# prozeda_0_1.net
KiCad netlist of a schematic drawn in EAGLE
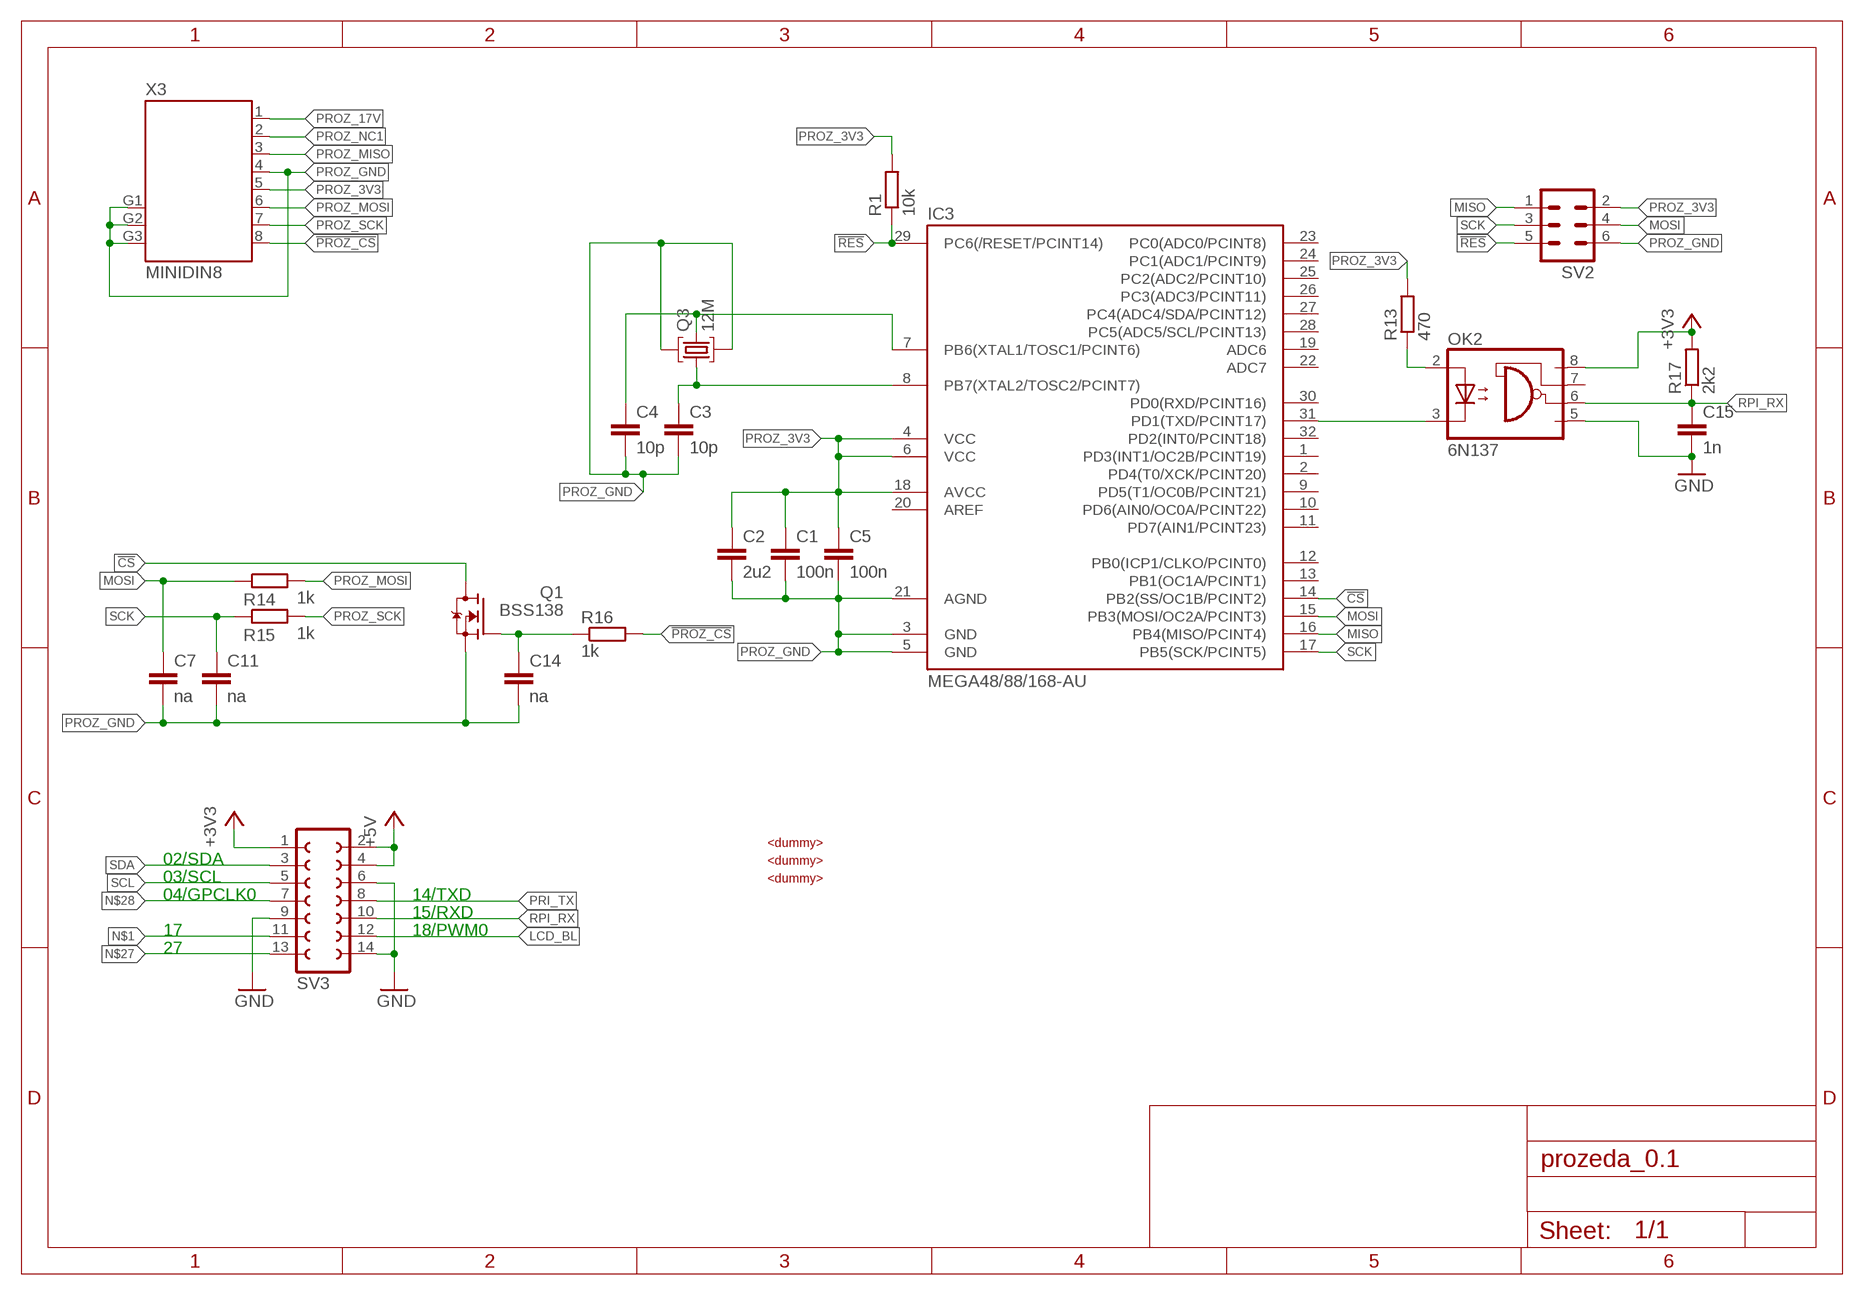
[diagram p0: schematic, sheet 1]

(export (version "E")
  (design (tool "Eeschema 10.0.6"))
  (components
    (comp (ref "C1")
      (value "100n")
      (footprint "eagle-import:C0603")
      (libsource (lib "eagle-import") (part "C-EUC0603"))
    )
    (comp (ref "C2")
      (value "2u2")
      (footprint "eagle-import:C0805")
      (libsource (lib "eagle-import") (part "C-EUC0805"))
    )
    (comp (ref "C3")
      (value "10p")
      (footprint "eagle-import:C0603")
      (libsource (lib "eagle-import") (part "C-EUC0603"))
    )
    (comp (ref "C4")
      (value "10p")
      (footprint "eagle-import:C0603")
      (libsource (lib "eagle-import") (part "C-EUC0603"))
    )
    (comp (ref "C5")
      (value "100n")
      (footprint "eagle-import:C0603")
      (libsource (lib "eagle-import") (part "C-EUC0603"))
    )
    (comp (ref "C7")
      (value "na")
      (footprint "eagle-import:C0603")
      (libsource (lib "eagle-import") (part "C-EUC0603"))
    )
    (comp (ref "C11")
      (value "na")
      (footprint "eagle-import:C0603")
      (libsource (lib "eagle-import") (part "C-EUC0603"))
    )
    (comp (ref "C14")
      (value "na")
      (footprint "eagle-import:C0603")
      (libsource (lib "eagle-import") (part "C-EUC0603"))
    )
    (comp (ref "C15")
      (value "1n")
      (footprint "eagle-import:C0603")
      (libsource (lib "eagle-import") (part "C-EUC0603"))
    )
    (comp (ref "IC3")
      (value "MEGA48/88/168-AU")
      (footprint "eagle-import:TQFP32-08")
      (libsource (lib "eagle-import") (part "MEGA48/88/168-AU"))
    )
    (comp (ref "OK2")
      (value "6N137")
      (footprint "eagle-import:DIL08")
      (libsource (lib "eagle-import") (part "6N137"))
    )
    (comp (ref "Q1")
      (value "BSS138")
      (footprint "eagle-import:SOT23")
      (libsource (lib "eagle-import") (part "BSS138"))
    )
    (comp (ref "Q3")
      (value "12M")
      (footprint "eagle-import:MJ")
      (libsource (lib "eagle-import") (part "SMD4PADMJ"))
    )
    (comp (ref "R1")
      (value "10k")
      (footprint "eagle-import:R0603")
      (libsource (lib "eagle-import") (part "R-EU_R0603"))
    )
    (comp (ref "R13")
      (value "470")
      (footprint "eagle-import:R0603")
      (libsource (lib "eagle-import") (part "R-EU_R0603"))
    )
    (comp (ref "R14")
      (value "1k")
      (footprint "eagle-import:R0603")
      (libsource (lib "eagle-import") (part "R-EU_R0603"))
    )
    (comp (ref "R15")
      (value "1k")
      (footprint "eagle-import:R0603")
      (libsource (lib "eagle-import") (part "R-EU_R0603"))
    )
    (comp (ref "R16")
      (value "1k")
      (footprint "eagle-import:R0603")
      (libsource (lib "eagle-import") (part "R-EU_R0603"))
    )
    (comp (ref "R17")
      (value "2k2")
      (footprint "eagle-import:R0603")
      (libsource (lib "eagle-import") (part "R-EU_R0603"))
    )
    (comp (ref "SV2")
      (value "MA03-2")
      (footprint "eagle-import:MA03-2")
      (libsource (lib "eagle-import") (part "MA03-2"))
    )
    (comp (ref "SV3")
      (value "FE07-2")
      (footprint "eagle-import:FE07-2")
      (libsource (lib "eagle-import") (part "FE07-2"))
    )
    (comp (ref "U$1")
      (value "DUMMY")
      (footprint "eagle-import:DUMMY")
      (libsource (lib "eagle-import") (part "DUMMY"))
    )
    (comp (ref "U$2")
      (value "DUMMY")
      (footprint "eagle-import:DUMMY")
      (libsource (lib "eagle-import") (part "DUMMY"))
    )
    (comp (ref "U$3")
      (value "DUMMY")
      (footprint "eagle-import:DUMMY")
      (libsource (lib "eagle-import") (part "DUMMY"))
    )
    (comp (ref "X3")
      (value "MINIDIN8")
      (footprint "eagle-import:MINI-DIN8")
      (libsource (lib "eagle-import") (part "MINIDIN8"))
    )
  )
  (nets
    (net (code "1") (name "+3V3") (class "Default")
      (node (ref "OK2") (pin "8") (pinfunction "VCC_8") (pintype "passive"))
      (node (ref "R17") (pin "2") (pinfunction "2_2") (pintype "passive"))
      (node (ref "SV3") (pin "1") (pinfunction "1_1") (pintype "passive"))
    )
    (net (code "2") (name "+5V") (class "Default")
      (node (ref "SV3") (pin "2") (pinfunction "2_2") (pintype "passive"))
      (node (ref "SV3") (pin "4") (pinfunction "4_4") (pintype "passive"))
    )
    (net (code "3") (name "/~{CS}") (class "Default")
      (node (ref "IC3") (pin "14") (pinfunction "PB2(SS/OC1B/PCINT2)_14") (pintype "bidirectional"))
      (node (ref "Q1") (pin "3") (pinfunction "D_3") (pintype "passive"))
    )
    (net (code "4") (name "/~{PROZ_CS}") (class "Default")
      (node (ref "R16") (pin "2") (pinfunction "2_2") (pintype "passive"))
      (node (ref "X3") (pin "8") (pinfunction "P$8_8") (pintype "bidirectional"))
    )
    (net (code "5") (name "/~{RES}") (class "Default")
      (node (ref "IC3") (pin "29") (pinfunction "PC6(/RESET/PCINT14)_29") (pintype "bidirectional"))
      (node (ref "R1") (pin "1") (pinfunction "1_1") (pintype "passive"))
      (node (ref "SV2") (pin "5") (pinfunction "5_5") (pintype "passive"))
    )
    (net (code "6") (name "GND") (class "Default")
      (node (ref "C15") (pin "2") (pinfunction "2_2") (pintype "passive"))
      (node (ref "OK2") (pin "5") (pinfunction "GND_5") (pintype "passive"))
      (node (ref "SV3") (pin "14") (pinfunction "14_14") (pintype "passive"))
      (node (ref "SV3") (pin "6") (pinfunction "6_6") (pintype "passive"))
      (node (ref "SV3") (pin "9") (pinfunction "9_9") (pintype "passive"))
    )
    (net (code "7") (name "LCD_BL") (class "Default")
      (node (ref "SV3") (pin "12") (pinfunction "12_12") (pintype "passive"))
    )
    (net (code "8") (name "MISO") (class "Default")
      (node (ref "IC3") (pin "16") (pinfunction "PB4(MISO/PCINT4)_16") (pintype "bidirectional"))
      (node (ref "SV2") (pin "1") (pinfunction "1_1") (pintype "passive"))
    )
    (net (code "9") (name "MOSI") (class "Default")
      (node (ref "C7") (pin "1") (pinfunction "1_1") (pintype "passive"))
      (node (ref "IC3") (pin "15") (pinfunction "PB3(MOSI/OC2A/PCINT3)_15") (pintype "bidirectional"))
      (node (ref "R14") (pin "1") (pinfunction "1_1") (pintype "passive"))
      (node (ref "SV2") (pin "4") (pinfunction "4_4") (pintype "passive"))
    )
    (net (code "10") (name "N$1") (class "Default")
      (node (ref "SV3") (pin "11") (pinfunction "11_11") (pintype "passive"))
    )
    (net (code "11") (name "N$27") (class "Default")
      (node (ref "SV3") (pin "13") (pinfunction "13_13") (pintype "passive"))
    )
    (net (code "12") (name "N$28") (class "Default")
      (node (ref "SV3") (pin "7") (pinfunction "7_7") (pintype "passive"))
    )
    (net (code "13") (name "Net-(IC3-PB6(XTAL1{slash}TOSC1{slash}PCINT6))") (class "Default")
      (node (ref "C4") (pin "1") (pinfunction "1_1") (pintype "passive"))
      (node (ref "IC3") (pin "7") (pinfunction "PB6(XTAL1/TOSC1/PCINT6)_7") (pintype "bidirectional"))
      (node (ref "Q3") (pin "3") (pinfunction "3_3") (pintype "passive"))
    )
    (net (code "14") (name "Net-(IC3-PB7(XTAL2{slash}TOSC2{slash}PCINT7))") (class "Default")
      (node (ref "C3") (pin "1") (pinfunction "1_1") (pintype "passive"))
      (node (ref "IC3") (pin "8") (pinfunction "PB7(XTAL2/TOSC2/PCINT7)_8") (pintype "bidirectional"))
      (node (ref "Q3") (pin "1") (pinfunction "1_1") (pintype "passive"))
    )
    (net (code "15") (name "Net-(IC3-PD1(TXD{slash}PCINT17))") (class "Default")
      (node (ref "IC3") (pin "31") (pinfunction "PD1(TXD/PCINT17)_31") (pintype "bidirectional"))
      (node (ref "OK2") (pin "3") (pinfunction "C_3") (pintype "passive"))
    )
    (net (code "16") (name "Net-(OK2-A)") (class "Default")
      (node (ref "OK2") (pin "2") (pinfunction "A_2") (pintype "passive"))
      (node (ref "R13") (pin "1") (pinfunction "1_1") (pintype "passive"))
    )
    (net (code "17") (name "Net-(Q1-G)") (class "Default")
      (node (ref "C14") (pin "1") (pinfunction "1_1") (pintype "passive"))
      (node (ref "Q1") (pin "1") (pinfunction "G_1") (pintype "passive"))
      (node (ref "R16") (pin "1") (pinfunction "1_1") (pintype "passive"))
    )
    (net (code "18") (name "PRI_TX") (class "Default")
      (node (ref "SV3") (pin "8") (pinfunction "8_8") (pintype "passive"))
    )
    (net (code "19") (name "PROZ_3V3") (class "Default")
      (node (ref "C1") (pin "1") (pinfunction "1_1") (pintype "passive"))
      (node (ref "C2") (pin "1") (pinfunction "1_1") (pintype "passive"))
      (node (ref "C5") (pin "1") (pinfunction "1_1") (pintype "passive"))
      (node (ref "IC3") (pin "18") (pinfunction "AVCC_18") (pintype "passive"))
      (node (ref "IC3") (pin "4") (pinfunction "VCC_4") (pintype "power_in"))
      (node (ref "IC3") (pin "6") (pinfunction "VCC_6") (pintype "power_in"))
      (node (ref "R1") (pin "2") (pinfunction "2_2") (pintype "passive"))
      (node (ref "R13") (pin "2") (pinfunction "2_2") (pintype "passive"))
      (node (ref "SV2") (pin "2") (pinfunction "2_2") (pintype "passive"))
      (node (ref "X3") (pin "5") (pinfunction "P$5_5") (pintype "bidirectional"))
    )
    (net (code "20") (name "PROZ_17V") (class "Default")
      (node (ref "X3") (pin "1") (pinfunction "P$1_1") (pintype "bidirectional"))
    )
    (net (code "21") (name "PROZ_GND") (class "Default")
      (node (ref "C1") (pin "2") (pinfunction "2_2") (pintype "passive"))
      (node (ref "C11") (pin "2") (pinfunction "2_2") (pintype "passive"))
      (node (ref "C14") (pin "2") (pinfunction "2_2") (pintype "passive"))
      (node (ref "C2") (pin "2") (pinfunction "2_2") (pintype "passive"))
      (node (ref "C3") (pin "2") (pinfunction "2_2") (pintype "passive"))
      (node (ref "C4") (pin "2") (pinfunction "2_2") (pintype "passive"))
      (node (ref "C5") (pin "2") (pinfunction "2_2") (pintype "passive"))
      (node (ref "C7") (pin "2") (pinfunction "2_2") (pintype "passive"))
      (node (ref "IC3") (pin "21") (pinfunction "AGND_21") (pintype "power_in"))
      (node (ref "IC3") (pin "3") (pinfunction "GND_3") (pintype "power_in"))
      (node (ref "IC3") (pin "5") (pinfunction "GND_5") (pintype "power_in"))
      (node (ref "Q1") (pin "2") (pinfunction "S_2") (pintype "passive"))
      (node (ref "Q3") (pin "2") (pinfunction "2_2") (pintype "passive"))
      (node (ref "Q3") (pin "4") (pinfunction "4_4") (pintype "passive"))
      (node (ref "SV2") (pin "6") (pinfunction "6_6") (pintype "passive"))
      (node (ref "X3") (pin "4") (pinfunction "P$4_4") (pintype "bidirectional"))
      (node (ref "X3") (pin "G1") (pinfunction "P$9_G1") (pintype "bidirectional"))
      (node (ref "X3") (pin "G2") (pinfunction "P$10_G2") (pintype "bidirectional"))
      (node (ref "X3") (pin "G3") (pinfunction "P$11_G3") (pintype "bidirectional"))
    )
    (net (code "22") (name "PROZ_MISO") (class "Default")
      (node (ref "X3") (pin "3") (pinfunction "P$3_3") (pintype "bidirectional"))
    )
    (net (code "23") (name "PROZ_MOSI") (class "Default")
      (node (ref "R14") (pin "2") (pinfunction "2_2") (pintype "passive"))
      (node (ref "X3") (pin "6") (pinfunction "P$6_6") (pintype "bidirectional"))
    )
    (net (code "24") (name "PROZ_NC1") (class "Default")
      (node (ref "X3") (pin "2") (pinfunction "P$2_2") (pintype "bidirectional"))
    )
    (net (code "25") (name "PROZ_SCK") (class "Default")
      (node (ref "R15") (pin "2") (pinfunction "2_2") (pintype "passive"))
      (node (ref "X3") (pin "7") (pinfunction "P$7_7") (pintype "bidirectional"))
    )
    (net (code "26") (name "RPI_RX") (class "Default")
      (node (ref "C15") (pin "1") (pinfunction "1_1") (pintype "passive"))
      (node (ref "OK2") (pin "6") (pinfunction "VO_6") (pintype "passive"))
      (node (ref "R17") (pin "1") (pinfunction "1_1") (pintype "passive"))
      (node (ref "SV3") (pin "10") (pinfunction "10_10") (pintype "passive"))
    )
    (net (code "27") (name "SCK") (class "Default")
      (node (ref "C11") (pin "1") (pinfunction "1_1") (pintype "passive"))
      (node (ref "IC3") (pin "17") (pinfunction "PB5(SCK/PCINT5)_17") (pintype "bidirectional"))
      (node (ref "R15") (pin "1") (pinfunction "1_1") (pintype "passive"))
      (node (ref "SV2") (pin "3") (pinfunction "3_3") (pintype "passive"))
    )
    (net (code "28") (name "SCL") (class "Default")
      (node (ref "SV3") (pin "5") (pinfunction "5_5") (pintype "passive"))
    )
    (net (code "29") (name "SDA") (class "Default")
      (node (ref "SV3") (pin "3") (pinfunction "3_3") (pintype "passive"))
    )
    (net (code "30") (name "unconnected-(IC3-ADC6-Pad19)") (class "Default")
      (node (ref "IC3") (pin "19") (pinfunction "ADC6_19") (pintype "passive"))
    )
    (net (code "31") (name "unconnected-(IC3-ADC7-Pad22)") (class "Default")
      (node (ref "IC3") (pin "22") (pinfunction "ADC7_22") (pintype "passive"))
    )
    (net (code "32") (name "unconnected-(IC3-AREF-Pad20)") (class "Default")
      (node (ref "IC3") (pin "20") (pinfunction "AREF_20") (pintype "passive"))
    )
    (net (code "33") (name "unconnected-(IC3-PB0(ICP1{slash}CLKO{slash}PCINT0)-Pad12)") (class "Default")
      (node (ref "IC3") (pin "12") (pinfunction "PB0(ICP1/CLKO/PCINT0)_12") (pintype "bidirectional"))
    )
    (net (code "34") (name "unconnected-(IC3-PB1(OC1A{slash}PCINT1)-Pad13)") (class "Default")
      (node (ref "IC3") (pin "13") (pinfunction "PB1(OC1A/PCINT1)_13") (pintype "bidirectional"))
    )
    (net (code "35") (name "unconnected-(IC3-PC0(ADC0{slash}PCINT8)-Pad23)") (class "Default")
      (node (ref "IC3") (pin "23") (pinfunction "PC0(ADC0/PCINT8)_23") (pintype "bidirectional"))
    )
    (net (code "36") (name "unconnected-(IC3-PC1(ADC1{slash}PCINT9)-Pad24)") (class "Default")
      (node (ref "IC3") (pin "24") (pinfunction "PC1(ADC1/PCINT9)_24") (pintype "bidirectional"))
    )
    (net (code "37") (name "unconnected-(IC3-PC2(ADC2{slash}PCINT10)-Pad25)") (class "Default")
      (node (ref "IC3") (pin "25") (pinfunction "PC2(ADC2/PCINT10)_25") (pintype "bidirectional"))
    )
    (net (code "38") (name "unconnected-(IC3-PC3(ADC3{slash}PCINT11)-Pad26)") (class "Default")
      (node (ref "IC3") (pin "26") (pinfunction "PC3(ADC3/PCINT11)_26") (pintype "bidirectional"))
    )
    (net (code "39") (name "unconnected-(IC3-PC4(ADC4{slash}SDA{slash}PCINT12)-Pad27)") (class "Default")
      (node (ref "IC3") (pin "27") (pinfunction "PC4(ADC4/SDA/PCINT12)_27") (pintype "bidirectional"))
    )
    (net (code "40") (name "unconnected-(IC3-PC5(ADC5{slash}SCL{slash}PCINT13)-Pad28)") (class "Default")
      (node (ref "IC3") (pin "28") (pinfunction "PC5(ADC5/SCL/PCINT13)_28") (pintype "bidirectional"))
    )
    (net (code "41") (name "unconnected-(IC3-PD0(RXD{slash}PCINT16)-Pad30)") (class "Default")
      (node (ref "IC3") (pin "30") (pinfunction "PD0(RXD/PCINT16)_30") (pintype "bidirectional"))
    )
    (net (code "42") (name "unconnected-(IC3-PD2(INT0{slash}PCINT18)-Pad32)") (class "Default")
      (node (ref "IC3") (pin "32") (pinfunction "PD2(INT0/PCINT18)_32") (pintype "bidirectional"))
    )
    (net (code "43") (name "unconnected-(IC3-PD3(INT1{slash}OC2B{slash}PCINT19)-Pad1)") (class "Default")
      (node (ref "IC3") (pin "1") (pinfunction "PD3(INT1/OC2B/PCINT19)_1") (pintype "bidirectional"))
    )
    (net (code "44") (name "unconnected-(IC3-PD4(T0{slash}XCK{slash}PCINT20)-Pad2)") (class "Default")
      (node (ref "IC3") (pin "2") (pinfunction "PD4(T0/XCK/PCINT20)_2") (pintype "bidirectional"))
    )
    (net (code "45") (name "unconnected-(IC3-PD5(T1{slash}OC0B{slash}PCINT21)-Pad9)") (class "Default")
      (node (ref "IC3") (pin "9") (pinfunction "PD5(T1/OC0B/PCINT21)_9") (pintype "bidirectional"))
    )
    (net (code "46") (name "unconnected-(IC3-PD6(AIN0{slash}OC0A{slash}PCINT22)-Pad10)") (class "Default")
      (node (ref "IC3") (pin "10") (pinfunction "PD6(AIN0/OC0A/PCINT22)_10") (pintype "bidirectional"))
    )
    (net (code "47") (name "unconnected-(IC3-PD7(AIN1{slash}PCINT23)-Pad11)") (class "Default")
      (node (ref "IC3") (pin "11") (pinfunction "PD7(AIN1/PCINT23)_11") (pintype "bidirectional"))
    )
    (net (code "48") (name "unconnected-(OK2-VE-Pad7)") (class "Default")
      (node (ref "OK2") (pin "7") (pinfunction "VE_7") (pintype "passive"))
    )
  )
)
